# Charger.net
KiCad netlist of a schematic drawn in Altium Designer
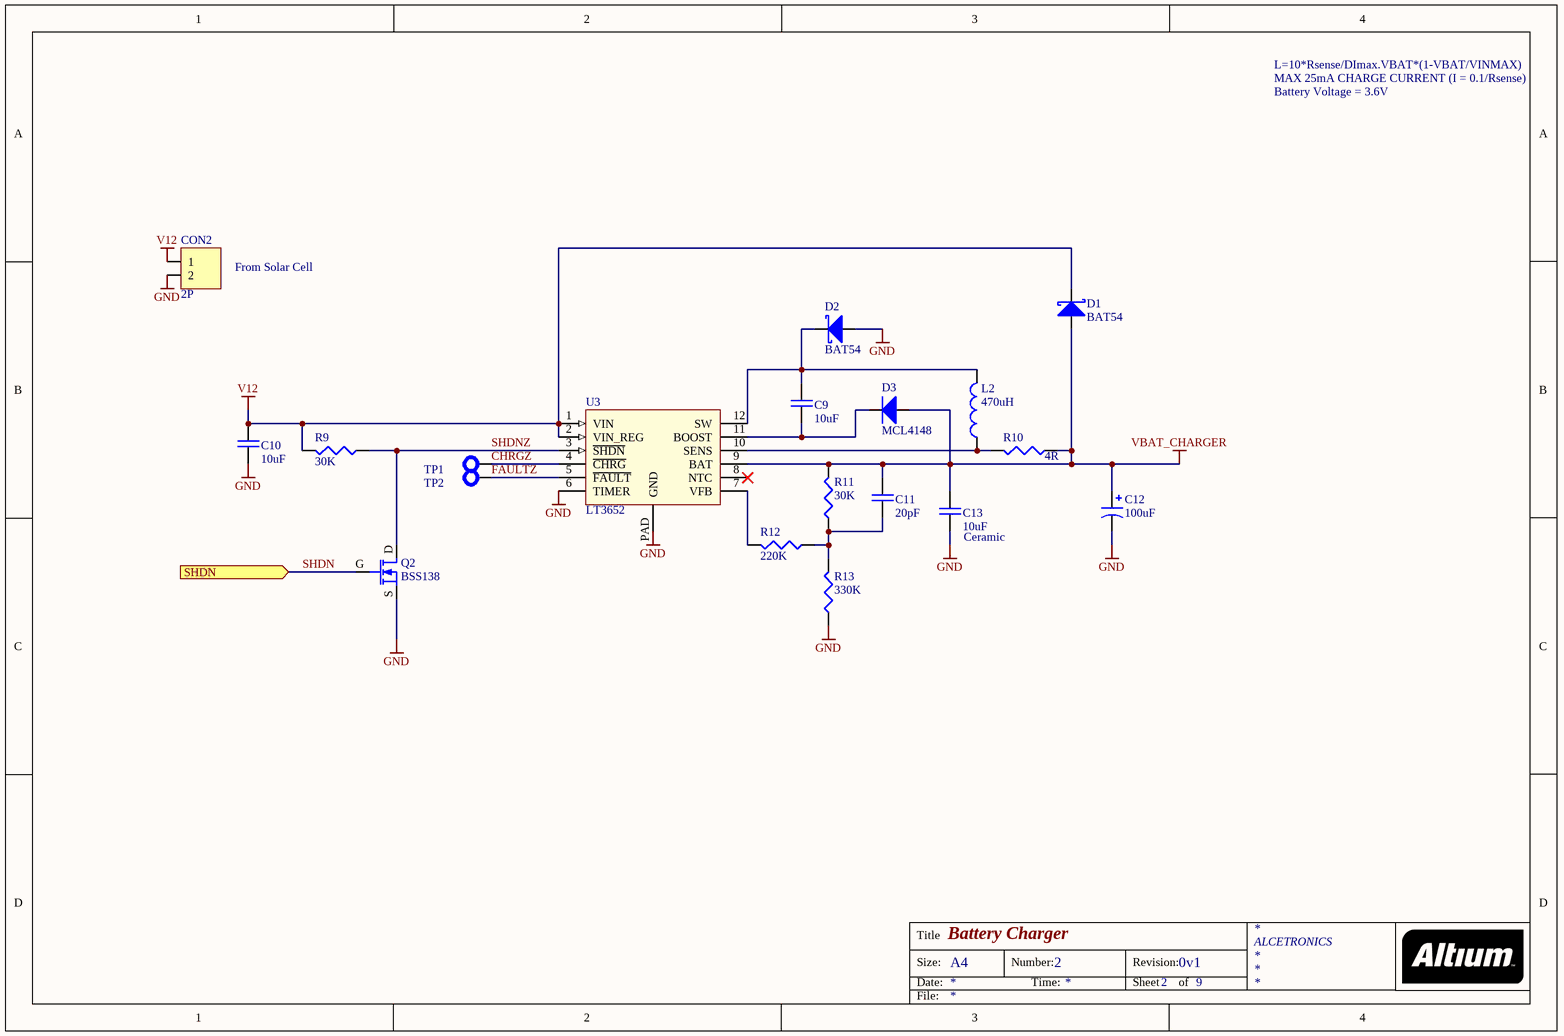
[diagram p0: Charger.SchDoc]

(export (version "E")
  (design (tool "Eeschema 10.0.6"))
  (components
    (comp (ref "C9")
      (value "10uF")
      (footprint "0805")
      (description "Capacitor")
      (fields (field (name "OWNER") "Nuno Brum"))
      (libsource (lib "Alcetronics_Devices") (part "CAP"))
    )
    (comp (ref "C10")
      (value "10uF")
      (footprint "0805")
      (description "Capacitor")
      (fields (field (name "OWNER") "Nuno Brum"))
      (libsource (lib "Alcetronics_Devices") (part "CAP"))
    )
    (comp (ref "C11")
      (value "20pF")
      (footprint "0603")
      (description "Capacitor")
      (fields (field (name "OWNER") "Nuno Brum"))
      (libsource (lib "Alcetronics_Devices") (part "CAP"))
    )
    (comp (ref "C12")
      (value "100uF")
      (footprint "RADIAL-5MM")
      (description "Polarized Capacitor")
      (fields (field (name "OWNER") "Nuno Brum"))
      (libsource (lib "Alcetronics_Devices") (part "CAP POL"))
    )
    (comp (ref "C13")
      (value "10uF")
      (footprint "0805")
      (description "Capacitor")
      (fields (field (name "OWNER") "Nuno Brum"))
      (libsource (lib "Alcetronics_Devices") (part "CAP"))
    )
    (comp (ref "CON2")
      (value "2P")
      (footprint "INTERLOCK2-5MM-FIXED")
      (description "Connector 2 pins")
      (fields (field (name "OWNER") "Rui Rebelo"))
      (libsource (lib "Alcetronics_EM") (part "CON02"))
    )
    (comp (ref "D1")
      (value "BAT54")
      (footprint "SOT-23@AK")
      (description "Small Signal Schottky Diode")
      (fields (field (name "OWNER") "Nuno Brum"))
      (libsource (lib "Alcetronics_Devices") (part "Diode Schottky"))
    )
    (comp (ref "D2")
      (value "BAT54")
      (footprint "SOT-23@AK")
      (description "Small Signal Schottky Diode")
      (fields (field (name "OWNER") "Nuno Brum"))
      (libsource (lib "Alcetronics_Devices") (part "Diode Schottky"))
    )
    (comp (ref "D3")
      (value "MCL4148")
      (footprint "0805@DIODE")
      (description "Vishay Standard Avalanche Sinterglass Diode")
      (fields (field (name "OWNER") "Nuno Brum"))
      (libsource (lib "Alcetronics_Devices") (part "Diode"))
    )
    (comp (ref "L2")
      (value "470uH")
      (footprint "12X12")
      (description "Inductor")
      (fields (field (name "OWNER") "Nuno Brum"))
      (libsource (lib "Alcetronics_Devices") (part "IND"))
    )
    (comp (ref "Q2")
      (value "BSS138")
      (footprint "SOT-23@GSD")
      (description "N-Channel Logic Level Enhancement Mode Field Effect Transistor")
      (fields (field (name "OWNER") "Nuno Brum"))
      (libsource (lib "Alcetronics_Devices") (part "MOSFET-N"))
    )
    (comp (ref "R9")
      (value "30K")
      (footprint "0603")
      (description "Resistor")
      (fields (field (name "OWNER") "Nuno Brum"))
      (libsource (lib "Alcetronics_Devices") (part "RES"))
    )
    (comp (ref "R10")
      (value "4R")
      (footprint "1206")
      (description "Resistor")
      (fields (field (name "OWNER") "Nuno Brum"))
      (libsource (lib "Alcetronics_Devices") (part "RES"))
    )
    (comp (ref "R11")
      (value "30K")
      (footprint "0603")
      (description "Resistor")
      (fields (field (name "OWNER") "Nuno Brum"))
      (libsource (lib "Alcetronics_Devices") (part "RES"))
    )
    (comp (ref "R12")
      (value "220K")
      (footprint "0603")
      (description "Resistor")
      (fields (field (name "OWNER") "Nuno Brum"))
      (libsource (lib "Alcetronics_Devices") (part "RES"))
    )
    (comp (ref "R13")
      (value "330K")
      (footprint "0603")
      (description "Resistor")
      (fields (field (name "OWNER") "Nuno Brum"))
      (libsource (lib "Alcetronics_Devices") (part "RES"))
    )
    (comp (ref "TP1")
      (value "Test Point")
      (footprint "TERMINAL")
      (description "Test/Probe Point")
      (fields (field (name "OWNER") "Nuno Brum"))
      (libsource (lib "Alcetronics_EM") (part "TEST-PROBE"))
    )
    (comp (ref "TP2")
      (value "Test Point")
      (footprint "TERMINAL")
      (description "Test/Probe Point")
      (fields (field (name "OWNER") "Nuno Brum"))
      (libsource (lib "Alcetronics_EM") (part "TEST-PROBE"))
    )
    (comp (ref "U3")
      (value "LT3652")
      (footprint "MSOP12@EP")
      (description "Power Tracking 2A Battery Charger for Solar Power")
      (libsource (lib "Alcetronics_IC") (part "LT3652"))
    )
  )
  (nets
    (net (code "1") (name "/CHRGZ") (class "Default")
      (node (ref "TP1") (pin "1") (pinfunction "TP_1") (pintype "passive"))
      (node (ref "U3") (pin "4") (pinfunction "~{CHRG}_4") (pintype "open_collector"))
    )
    (net (code "2") (name "/FAULTZ") (class "Default")
      (node (ref "TP2") (pin "1") (pinfunction "TP_1") (pintype "passive"))
      (node (ref "U3") (pin "5") (pinfunction "~{FAULT}_5") (pintype "open_collector"))
    )
    (net (code "3") (name "/SHDN") (class "Default")
      (node (ref "Q2") (pin "G") (pinfunction "G_G") (pintype "passive"))
    )
    (net (code "4") (name "/SHDNZ") (class "Default")
      (node (ref "Q2") (pin "D") (pinfunction "D_D") (pintype "passive"))
      (node (ref "R9") (pin "1") (pinfunction "1_1") (pintype "passive"))
      (node (ref "U3") (pin "3") (pinfunction "~{SHDN}_3") (pintype "input"))
    )
    (net (code "5") (name "GND") (class "Default")
      (node (ref "C10") (pin "1") (pinfunction "1_1") (pintype "passive"))
      (node (ref "C12") (pin "2") (pinfunction "N_2") (pintype "passive"))
      (node (ref "C13") (pin "1") (pinfunction "1_1") (pintype "passive"))
      (node (ref "CON2") (pin "2") (pinfunction "2_2") (pintype "passive"))
      (node (ref "D2") (pin "A") (pinfunction "A_A") (pintype "passive"))
      (node (ref "Q2") (pin "S") (pinfunction "S_S") (pintype "passive"))
      (node (ref "R13") (pin "1") (pinfunction "1_1") (pintype "passive"))
      (node (ref "U3") (pin "6") (pinfunction "TIMER_6") (pintype "passive"))
      (node (ref "U3") (pin "PAD") (pinfunction "GND_PAD") (pintype "passive"))
    )
    (net (code "6") (name "Net-(C11-Pad1)") (class "Default")
      (node (ref "C11") (pin "1") (pinfunction "1_1") (pintype "passive"))
      (node (ref "R11") (pin "1") (pinfunction "1_1") (pintype "passive"))
      (node (ref "R12") (pin "1") (pinfunction "1_1") (pintype "passive"))
      (node (ref "R13") (pin "2") (pinfunction "2_2") (pintype "passive"))
    )
    (net (code "7") (name "Net-(U3-BOOST)") (class "Default")
      (node (ref "C9") (pin "1") (pinfunction "1_1") (pintype "passive"))
      (node (ref "D3") (pin "K") (pinfunction "K_K") (pintype "passive"))
      (node (ref "U3") (pin "11") (pinfunction "BOOST_11") (pintype "passive"))
    )
    (net (code "8") (name "Net-(U3-SENS)") (class "Default")
      (node (ref "L2") (pin "1") (pinfunction "1_1") (pintype "passive"))
      (node (ref "R10") (pin "2") (pinfunction "2_2") (pintype "passive"))
      (node (ref "U3") (pin "10") (pinfunction "SENS_10") (pintype "passive"))
    )
    (net (code "9") (name "Net-(U3-SW)") (class "Default")
      (node (ref "C9") (pin "2") (pinfunction "2_2") (pintype "passive"))
      (node (ref "D2") (pin "K") (pinfunction "K_K") (pintype "passive"))
      (node (ref "L2") (pin "2") (pinfunction "2_2") (pintype "passive"))
      (node (ref "U3") (pin "12") (pinfunction "SW_12") (pintype "passive"))
    )
    (net (code "10") (name "Net-(U3-VFB)") (class "Default")
      (node (ref "R12") (pin "2") (pinfunction "2_2") (pintype "passive"))
      (node (ref "U3") (pin "7") (pinfunction "VFB_7") (pintype "passive"))
    )
    (net (code "11") (name "V12") (class "Default")
      (node (ref "C10") (pin "2") (pinfunction "2_2") (pintype "passive"))
      (node (ref "CON2") (pin "1") (pinfunction "1_1") (pintype "passive"))
      (node (ref "D1") (pin "K") (pinfunction "K_K") (pintype "passive"))
      (node (ref "R9") (pin "2") (pinfunction "2_2") (pintype "passive"))
      (node (ref "U3") (pin "1") (pinfunction "VIN_1") (pintype "input"))
      (node (ref "U3") (pin "2") (pinfunction "VIN_REG_2") (pintype "input"))
    )
    (net (code "12") (name "VBAT_CHARGER") (class "Default")
      (node (ref "C11") (pin "2") (pinfunction "2_2") (pintype "passive"))
      (node (ref "C12") (pin "1") (pinfunction "P_1") (pintype "passive"))
      (node (ref "C13") (pin "2") (pinfunction "2_2") (pintype "passive"))
      (node (ref "D1") (pin "A") (pinfunction "A_A") (pintype "passive"))
      (node (ref "D3") (pin "A") (pinfunction "A_A") (pintype "passive"))
      (node (ref "R10") (pin "1") (pinfunction "1_1") (pintype "passive"))
      (node (ref "R11") (pin "2") (pinfunction "2_2") (pintype "passive"))
      (node (ref "U3") (pin "9") (pinfunction "BAT_9") (pintype "power_in"))
    )
    (net (code "13") (name "unconnected-(U3-NTC-Pad8)") (class "Default")
      (node (ref "U3") (pin "8") (pinfunction "NTC_8") (pintype "passive+no_connect"))
    )
  )
)
